# musicbox.net
KiCad netlist of a schematic drawn in EAGLE
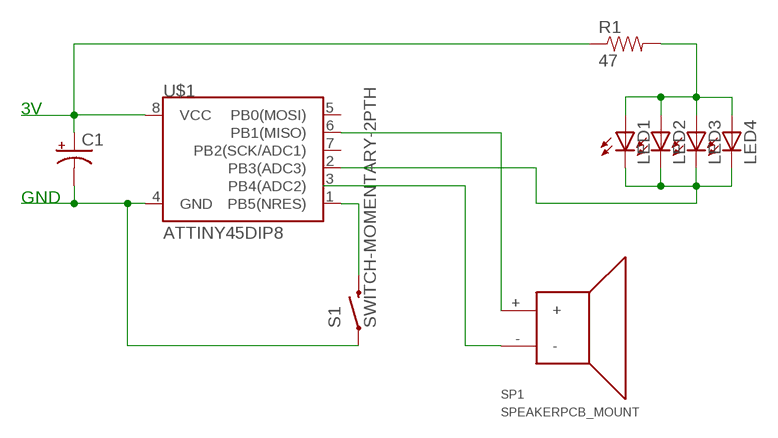
[diagram p0: schematic, sheet 1]

(export (version "E")
  (design (tool "Eeschema 10.0.6"))
  (components
    (comp (ref "C1")
      (value "CAP_POLPTH2")
      (footprint "eagle-import:CPOL-RADIAL-10UF-25V")
      (libsource (lib "eagle-import") (part "CAP_POLPTH2"))
    )
    (comp (ref "LED1")
      (value "LED5MM")
      (footprint "eagle-import:LED5MM")
      (libsource (lib "eagle-import") (part "LED5MM"))
    )
    (comp (ref "LED2")
      (value "LED5MM")
      (footprint "eagle-import:LED5MM")
      (libsource (lib "eagle-import") (part "LED5MM"))
    )
    (comp (ref "LED3")
      (value "LED5MM")
      (footprint "eagle-import:LED5MM")
      (libsource (lib "eagle-import") (part "LED5MM"))
    )
    (comp (ref "LED4")
      (value "LED5MM")
      (footprint "eagle-import:LED5MM")
      (libsource (lib "eagle-import") (part "LED5MM"))
    )
    (comp (ref "R1")
      (value "47")
      (footprint "eagle-import:1_6W-RES")
      (libsource (lib "eagle-import") (part "RESISTORPTH-1/6W"))
    )
    (comp (ref "S1")
      (value "SWITCH-MOMENTARY-2PTH")
      (footprint "eagle-import:TACTILE-PTH")
      (libsource (lib "eagle-import") (part "SWITCH-MOMENTARY-2PTH"))
    )
    (comp (ref "SP1")
      (value "SPEAKERPCB_MOUNT")
      (footprint "eagle-import:PCB_MOUNT_SPEAKER")
      (fields (field (name "MFG") "SANCO"))
      (libsource (lib "eagle-import") (part "SPEAKERPCB_MOUNT"))
    )
    (comp (ref "U$1")
      (value "ATTINY45DIP8")
      (footprint "eagle-import:DIP08")
      (libsource (lib "eagle-import") (part "ATTINY45DIP8"))
    )
  )
  (nets
    (net (code "1") (name "Net-(C1-+)") (class "Default")
      (node (ref "C1") (pin "1") (pinfunction "+_1") (pintype "passive"))
      (node (ref "R1") (pin "1") (pinfunction "1_1") (pintype "passive"))
      (node (ref "U$1") (pin "8") (pinfunction "VCC_8") (pintype "bidirectional"))
    )
    (net (code "2") (name "Net-(C1--)") (class "Default")
      (node (ref "C1") (pin "2") (pinfunction "-_2") (pintype "passive"))
      (node (ref "S1") (pin "1") (pinfunction "1_1") (pintype "passive"))
      (node (ref "U$1") (pin "4") (pinfunction "GND_4") (pintype "bidirectional"))
    )
    (net (code "3") (name "Net-(LED1-C)") (class "Default")
      (node (ref "LED1") (pin "K") (pinfunction "C_K") (pintype "passive"))
      (node (ref "LED2") (pin "K") (pinfunction "C_K") (pintype "passive"))
      (node (ref "LED3") (pin "K") (pinfunction "C_K") (pintype "passive"))
      (node (ref "LED4") (pin "K") (pinfunction "C_K") (pintype "passive"))
      (node (ref "U$1") (pin "2") (pinfunction "PB3(ADC3)_2") (pintype "bidirectional"))
    )
    (net (code "4") (name "Net-(LED1-PadA)") (class "Default")
      (node (ref "LED1") (pin "A") (pinfunction "A_A") (pintype "passive"))
      (node (ref "LED2") (pin "A") (pinfunction "A_A") (pintype "passive"))
      (node (ref "LED3") (pin "A") (pinfunction "A_A") (pintype "passive"))
      (node (ref "LED4") (pin "A") (pinfunction "A_A") (pintype "passive"))
      (node (ref "R1") (pin "2") (pinfunction "2_2") (pintype "passive"))
    )
    (net (code "5") (name "Net-(S1-2)") (class "Default")
      (node (ref "S1") (pin "3") (pinfunction "2_3") (pintype "passive"))
      (node (ref "U$1") (pin "1") (pinfunction "PB5(NRES)_1") (pintype "bidirectional"))
    )
    (net (code "6") (name "Net-(U$1-PB1(MISO))") (class "Default")
      (node (ref "SP1") (pin "+") (pinfunction "+_+") (pintype "bidirectional"))
      (node (ref "U$1") (pin "6") (pinfunction "PB1(MISO)_6") (pintype "bidirectional"))
    )
    (net (code "7") (name "unconnected-(SP1-Pad-)") (class "Default")
      (node (ref "SP1") (pin "-") (pinfunction "-_-") (pintype "bidirectional"))
    )
    (net (code "8") (name "unconnected-(U$1-PB0(MOSI)-Pad5)") (class "Default")
      (node (ref "U$1") (pin "5") (pinfunction "PB0(MOSI)_5") (pintype "bidirectional"))
    )
    (net (code "9") (name "unconnected-(U$1-PB2(SCK{slash}ADC1)-Pad7)") (class "Default")
      (node (ref "U$1") (pin "7") (pinfunction "PB2(SCK/ADC1)_7") (pintype "bidirectional"))
    )
    (net (code "10") (name "unconnected-(U$1-PB4(ADC2)-Pad3)") (class "Default")
      (node (ref "U$1") (pin "3") (pinfunction "PB4(ADC2)_3") (pintype "bidirectional"))
    )
  )
)
